# IRComms.net
KiCad netlist of a schematic drawn in Altium Designer
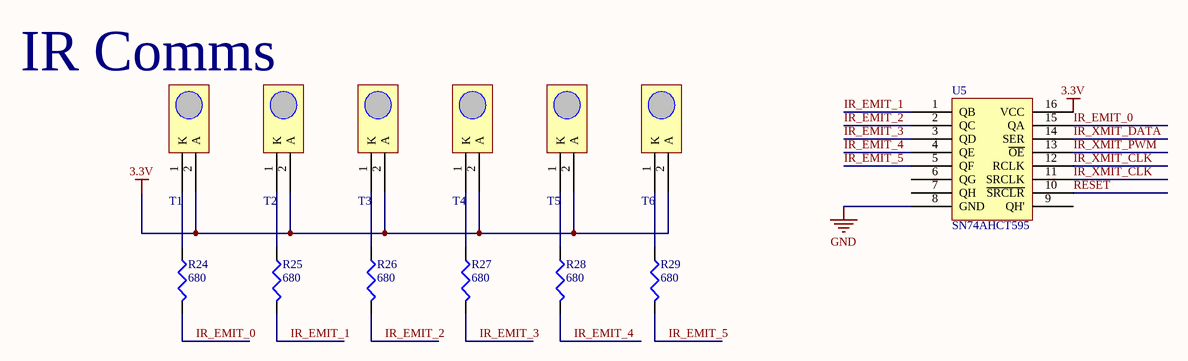
[diagram p0: IRComms.SchDoc]

(export (version "E")
  (design (tool "Eeschema 10.0.6"))
  (components
    (comp (ref "R24")
      (value "680")
      (footprint "RESC1608L")
      (description "Resistor")
      (fields (field (name "Comment") "Res3") (field (name "PUBLISHER") "Altium Limited"))
      (libsource (lib "Miscellaneous Devices") (part "Res3"))
    )
    (comp (ref "R25")
      (value "680")
      (footprint "RESC1608L")
      (description "Resistor")
      (fields (field (name "Comment") "Res3") (field (name "PUBLISHER") "Altium Limited"))
      (libsource (lib "Miscellaneous Devices") (part "Res3"))
    )
    (comp (ref "R26")
      (value "680")
      (footprint "RESC1608L")
      (description "Resistor")
      (fields (field (name "Comment") "Res3") (field (name "PUBLISHER") "Altium Limited"))
      (libsource (lib "Miscellaneous Devices") (part "Res3"))
    )
    (comp (ref "R27")
      (value "680")
      (footprint "RESC1608L")
      (description "Resistor")
      (fields (field (name "Comment") "Res3") (field (name "PUBLISHER") "Altium Limited"))
      (libsource (lib "Miscellaneous Devices") (part "Res3"))
    )
    (comp (ref "R28")
      (value "680")
      (footprint "RESC1608L")
      (description "Resistor")
      (fields (field (name "Comment") "Res3") (field (name "PUBLISHER") "Altium Limited"))
      (libsource (lib "Miscellaneous Devices") (part "Res3"))
    )
    (comp (ref "R29")
      (value "680")
      (footprint "RESC1608L")
      (description "Resistor")
      (fields (field (name "Comment") "Res3") (field (name "PUBLISHER") "Altium Limited"))
      (libsource (lib "Miscellaneous Devices") (part "Res3"))
    )
    (comp (ref "T1") (value "LN54") (footprint "LN54") (libsource (lib "mrone") (part "LN54")))
    (comp (ref "T2") (value "LN54") (footprint "LN54") (libsource (lib "mrone") (part "LN54")))
    (comp (ref "T3") (value "LN54") (footprint "LN54") (libsource (lib "mrone") (part "LN54")))
    (comp (ref "T4") (value "LN54") (footprint "LN54") (libsource (lib "mrone") (part "LN54")))
    (comp (ref "T5") (value "LN54") (footprint "LN54") (libsource (lib "mrone") (part "LN54")))
    (comp (ref "T6") (value "LN54") (footprint "LN54") (libsource (lib "mrone") (part "LN54")))
    (comp (ref "U5")
      (value "SN74AHCT595")
      (footprint "TSSOP-16")
      (description "shift register")
      (libsource (lib "mrone") (part "SN74AHCT595"))
    )
  )
  (nets
    (net (code "1") (name "/IR_EMIT_0") (class "Default")
      (node (ref "R24") (pin "2") (pinfunction "2_2") (pintype "passive"))
      (node (ref "U5") (pin "15") (pinfunction "QA_15") (pintype "passive"))
    )
    (net (code "2") (name "/IR_EMIT_1") (class "Default")
      (node (ref "R25") (pin "2") (pinfunction "2_2") (pintype "passive"))
      (node (ref "U5") (pin "1") (pinfunction "QB_1") (pintype "passive"))
    )
    (net (code "3") (name "/IR_EMIT_2") (class "Default")
      (node (ref "R26") (pin "2") (pinfunction "2_2") (pintype "passive"))
      (node (ref "U5") (pin "2") (pinfunction "QC_2") (pintype "passive"))
    )
    (net (code "4") (name "/IR_EMIT_3") (class "Default")
      (node (ref "R27") (pin "2") (pinfunction "2_2") (pintype "passive"))
      (node (ref "U5") (pin "3") (pinfunction "QD_3") (pintype "passive"))
    )
    (net (code "5") (name "/IR_EMIT_4") (class "Default")
      (node (ref "R28") (pin "2") (pinfunction "2_2") (pintype "passive"))
      (node (ref "U5") (pin "4") (pinfunction "QE_4") (pintype "passive"))
    )
    (net (code "6") (name "/IR_EMIT_5") (class "Default")
      (node (ref "R29") (pin "2") (pinfunction "2_2") (pintype "passive"))
      (node (ref "U5") (pin "5") (pinfunction "QF_5") (pintype "passive"))
    )
    (net (code "7") (name "/IR_XMIT_CLK") (class "Default")
      (node (ref "U5") (pin "11") (pinfunction "SRCLK_11") (pintype "passive"))
      (node (ref "U5") (pin "12") (pinfunction "RCLK_12") (pintype "passive"))
    )
    (net (code "8") (name "/IR_XMIT_DATA") (class "Default")
      (node (ref "U5") (pin "14") (pinfunction "SER_14") (pintype "passive"))
    )
    (net (code "9") (name "/IR_XMIT_PWM") (class "Default")
      (node (ref "U5") (pin "13") (pinfunction "~{OE}_13") (pintype "passive"))
    )
    (net (code "10") (name "/RESET") (class "Default")
      (node (ref "U5") (pin "10") (pinfunction "~{SRCLR}_10") (pintype "passive"))
    )
    (net (code "11") (name "3.3V") (class "Default")
      (node (ref "T1") (pin "2") (pinfunction "A_2") (pintype "passive"))
      (node (ref "T2") (pin "2") (pinfunction "A_2") (pintype "passive"))
      (node (ref "T3") (pin "2") (pinfunction "A_2") (pintype "passive"))
      (node (ref "T4") (pin "2") (pinfunction "A_2") (pintype "passive"))
      (node (ref "T5") (pin "2") (pinfunction "A_2") (pintype "passive"))
      (node (ref "T6") (pin "2") (pinfunction "A_2") (pintype "passive"))
      (node (ref "U5") (pin "16") (pinfunction "VCC_16") (pintype "passive"))
    )
    (net (code "12") (name "GND") (class "Default")
      (node (ref "U5") (pin "8") (pinfunction "GND_8") (pintype "passive"))
    )
    (net (code "13") (name "Net-(T1-K)") (class "Default")
      (node (ref "R24") (pin "1") (pinfunction "1_1") (pintype "passive"))
      (node (ref "T1") (pin "1") (pinfunction "K_1") (pintype "passive"))
    )
    (net (code "14") (name "Net-(T2-K)") (class "Default")
      (node (ref "R25") (pin "1") (pinfunction "1_1") (pintype "passive"))
      (node (ref "T2") (pin "1") (pinfunction "K_1") (pintype "passive"))
    )
    (net (code "15") (name "Net-(T3-K)") (class "Default")
      (node (ref "R26") (pin "1") (pinfunction "1_1") (pintype "passive"))
      (node (ref "T3") (pin "1") (pinfunction "K_1") (pintype "passive"))
    )
    (net (code "16") (name "Net-(T4-K)") (class "Default")
      (node (ref "R27") (pin "1") (pinfunction "1_1") (pintype "passive"))
      (node (ref "T4") (pin "1") (pinfunction "K_1") (pintype "passive"))
    )
    (net (code "17") (name "Net-(T5-K)") (class "Default")
      (node (ref "R28") (pin "1") (pinfunction "1_1") (pintype "passive"))
      (node (ref "T5") (pin "1") (pinfunction "K_1") (pintype "passive"))
    )
    (net (code "18") (name "Net-(T6-K)") (class "Default")
      (node (ref "R29") (pin "1") (pinfunction "1_1") (pintype "passive"))
      (node (ref "T6") (pin "1") (pinfunction "K_1") (pintype "passive"))
    )
    (net (code "19") (name "unconnected-(U5-QG-Pad6)") (class "Default")
      (node (ref "U5") (pin "6") (pinfunction "QG_6") (pintype "passive"))
    )
    (net (code "20") (name "unconnected-(U5-QH'-Pad9)") (class "Default")
      (node (ref "U5") (pin "9") (pinfunction "QH'_9") (pintype "passive"))
    )
    (net (code "21") (name "unconnected-(U5-QH-Pad7)") (class "Default")
      (node (ref "U5") (pin "7") (pinfunction "QH_7") (pintype "passive"))
    )
  )
)
